# pcb_telemetria.net
KiCad netlist of a schematic drawn in EAGLE
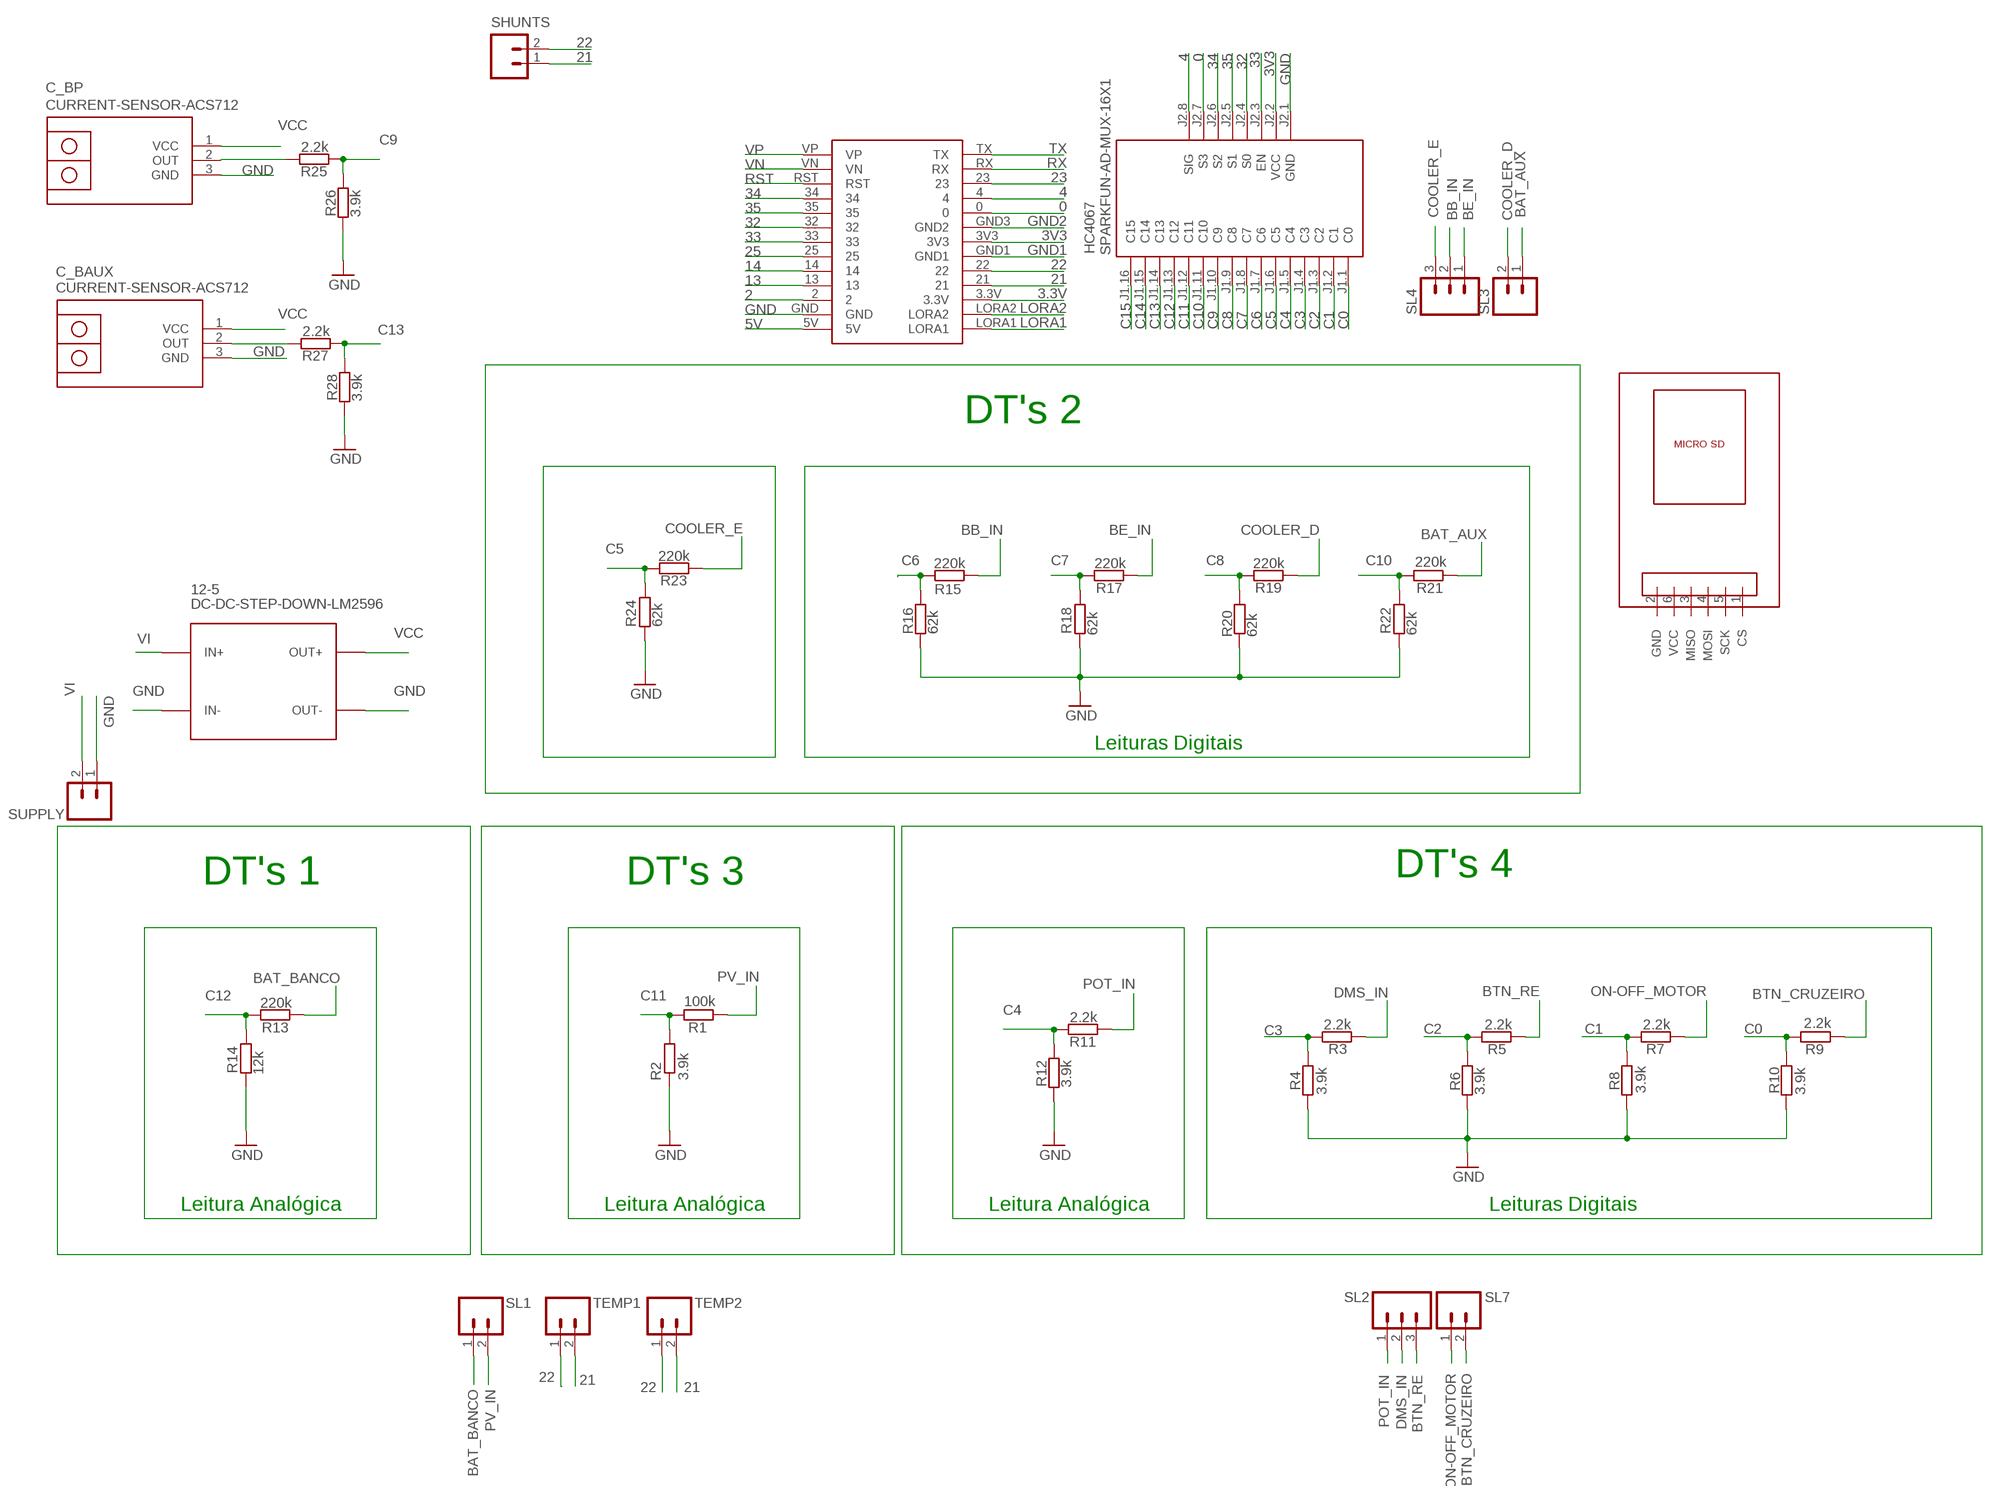
[diagram p0: schematic, sheet 1]

(export (version "E")
  (design (tool "Eeschema 10.0.6"))
  (components
    (comp (ref "12-5")
      (value "DC-DC-STEP-DOWN-LM2596")
      (footprint "eagle-import:DC-DC-STEP-DOWN-LM2596")
      (libsource (lib "eagle-import") (part "DC-DC-STEP-DOWN-LM2596"))
    )
    (comp (ref "C_BAUX")
      (value "CURRENT-SENSOR-ACS712")
      (footprint "eagle-import:CURRENT-SENSOR-ACS712")
      (libsource (lib "eagle-import") (part "CURRENT-SENSOR-ACS712"))
    )
    (comp (ref "C_BP")
      (value "CURRENT-SENSOR-ACS712")
      (footprint "eagle-import:CURRENT-SENSOR-ACS712")
      (libsource (lib "eagle-import") (part "CURRENT-SENSOR-ACS712"))
    )
    (comp (ref "HC4067")
      (value "SPARKFUN-AD-MUX-16X1")
      (footprint "eagle-import:SPARKFUN-AD-MUX-16X1")
      (libsource (lib "eagle-import") (part "SPARKFUN-AD-MUX-16X1"))
    )
    (comp (ref "R1")
      (value "100k")
      (footprint "eagle-import:0204_7")
      (libsource (lib "eagle-import") (part "R-EU_0204/7"))
    )
    (comp (ref "R2")
      (value "3.9k")
      (footprint "eagle-import:0204_7")
      (libsource (lib "eagle-import") (part "R-EU_0204/7"))
    )
    (comp (ref "R3")
      (value "2.2k")
      (footprint "eagle-import:0204_7")
      (libsource (lib "eagle-import") (part "R-EU_0204/7"))
    )
    (comp (ref "R4")
      (value "3.9k")
      (footprint "eagle-import:0204_7")
      (libsource (lib "eagle-import") (part "R-EU_0204/7"))
    )
    (comp (ref "R5")
      (value "2.2k")
      (footprint "eagle-import:0204_7")
      (libsource (lib "eagle-import") (part "R-EU_0204/7"))
    )
    (comp (ref "R6")
      (value "3.9k")
      (footprint "eagle-import:0204_7")
      (libsource (lib "eagle-import") (part "R-EU_0204/7"))
    )
    (comp (ref "R7")
      (value "2.2k")
      (footprint "eagle-import:0204_7")
      (libsource (lib "eagle-import") (part "R-EU_0204/7"))
    )
    (comp (ref "R8")
      (value "3.9k")
      (footprint "eagle-import:0204_7")
      (libsource (lib "eagle-import") (part "R-EU_0204/7"))
    )
    (comp (ref "R9")
      (value "2.2k")
      (footprint "eagle-import:0204_7")
      (libsource (lib "eagle-import") (part "R-EU_0204/7"))
    )
    (comp (ref "R10")
      (value "3.9k")
      (footprint "eagle-import:0204_7")
      (libsource (lib "eagle-import") (part "R-EU_0204/7"))
    )
    (comp (ref "R11")
      (value "2.2k")
      (footprint "eagle-import:0204_7")
      (libsource (lib "eagle-import") (part "R-EU_0204/7"))
    )
    (comp (ref "R12")
      (value "3.9k")
      (footprint "eagle-import:0204_7")
      (libsource (lib "eagle-import") (part "R-EU_0204/7"))
    )
    (comp (ref "R13")
      (value "220k")
      (footprint "eagle-import:0204_7")
      (libsource (lib "eagle-import") (part "R-EU_0204/7"))
    )
    (comp (ref "R14")
      (value "12k")
      (footprint "eagle-import:0204_7")
      (libsource (lib "eagle-import") (part "R-EU_0204/7"))
    )
    (comp (ref "R15")
      (value "220k")
      (footprint "eagle-import:0204_7")
      (libsource (lib "eagle-import") (part "R-EU_0204/7"))
    )
    (comp (ref "R16")
      (value "62k")
      (footprint "eagle-import:0204_7")
      (libsource (lib "eagle-import") (part "R-EU_0204/7"))
    )
    (comp (ref "R17")
      (value "220k")
      (footprint "eagle-import:0204_7")
      (libsource (lib "eagle-import") (part "R-EU_0204/7"))
    )
    (comp (ref "R18")
      (value "62k")
      (footprint "eagle-import:0204_7")
      (libsource (lib "eagle-import") (part "R-EU_0204/7"))
    )
    (comp (ref "R19")
      (value "220k")
      (footprint "eagle-import:0204_7")
      (libsource (lib "eagle-import") (part "R-EU_0204/7"))
    )
    (comp (ref "R20")
      (value "62k")
      (footprint "eagle-import:0204_7")
      (libsource (lib "eagle-import") (part "R-EU_0204/7"))
    )
    (comp (ref "R21")
      (value "220k")
      (footprint "eagle-import:0204_7")
      (libsource (lib "eagle-import") (part "R-EU_0204/7"))
    )
    (comp (ref "R22")
      (value "62k")
      (footprint "eagle-import:0204_7")
      (libsource (lib "eagle-import") (part "R-EU_0204/7"))
    )
    (comp (ref "R23")
      (value "220k")
      (footprint "eagle-import:0204_7")
      (libsource (lib "eagle-import") (part "R-EU_0204/7"))
    )
    (comp (ref "R24")
      (value "62k")
      (footprint "eagle-import:0204_7")
      (libsource (lib "eagle-import") (part "R-EU_0204/7"))
    )
    (comp (ref "R25")
      (value "2.2k")
      (footprint "eagle-import:0204_7")
      (libsource (lib "eagle-import") (part "R-EU_0204/7"))
    )
    (comp (ref "R26")
      (value "3.9k")
      (footprint "eagle-import:0204_7")
      (libsource (lib "eagle-import") (part "R-EU_0204/7"))
    )
    (comp (ref "R27")
      (value "2.2k")
      (footprint "eagle-import:0204_7")
      (libsource (lib "eagle-import") (part "R-EU_0204/7"))
    )
    (comp (ref "R28")
      (value "3.9k")
      (footprint "eagle-import:0204_7")
      (libsource (lib "eagle-import") (part "R-EU_0204/7"))
    )
    (comp (ref "SHUNTS")
      (value "M02")
      (footprint "eagle-import:02P")
      (libsource (lib "eagle-import") (part "M02"))
    )
    (comp (ref "SL1")
      (value "M02")
      (footprint "eagle-import:02P")
      (libsource (lib "eagle-import") (part "M02"))
    )
    (comp (ref "SL2")
      (value "M03")
      (footprint "eagle-import:03P")
      (libsource (lib "eagle-import") (part "M03"))
    )
    (comp (ref "SL3")
      (value "M02")
      (footprint "eagle-import:02P")
      (libsource (lib "eagle-import") (part "M02"))
    )
    (comp (ref "SL4")
      (value "M03")
      (footprint "eagle-import:03P")
      (libsource (lib "eagle-import") (part "M03"))
    )
    (comp (ref "SL7")
      (value "M02")
      (footprint "eagle-import:02P")
      (libsource (lib "eagle-import") (part "M02"))
    )
    (comp (ref "SUPPLY")
      (value "M02")
      (footprint "eagle-import:02P")
      (libsource (lib "eagle-import") (part "M02"))
    )
    (comp (ref "TEMP1")
      (value "M02")
      (footprint "eagle-import:02P")
      (libsource (lib "eagle-import") (part "M02"))
    )
    (comp (ref "TEMP2")
      (value "M02")
      (footprint "eagle-import:02P")
      (libsource (lib "eagle-import") (part "M02"))
    )
    (comp (ref "U$1")
      (value "TTGOBEAM")
      (footprint "eagle-import:TTGOBEAM")
      (libsource (lib "eagle-import") (part "TTGOBEAM"))
    )
    (comp (ref "U$2")
      (value "MICRO_SD_MODULE")
      (footprint "eagle-import:MICRO_SD")
      (libsource (lib "eagle-import") (part "MICRO_SD_MODULE"))
    )
  )
  (nets
    (net (code "1") (name "/0") (class "Default")
      (node (ref "HC4067") (pin "J2.7") (pinfunction "S3_J2.7") (pintype "bidirectional"))
      (node (ref "U$1") (pin "0") (pinfunction "0_0") (pintype "bidirectional"))
    )
    (net (code "2") (name "/2") (class "Default")
      (node (ref "U$1") (pin "2") (pinfunction "2_2") (pintype "bidirectional"))
    )
    (net (code "3") (name "/3.3V") (class "Default")
      (node (ref "U$1") (pin "3.3V") (pinfunction "3.3V_3.3V") (pintype "bidirectional"))
    )
    (net (code "4") (name "/3V3") (class "Default")
      (node (ref "HC4067") (pin "J2.2") (pinfunction "VCC_J2.2") (pintype "power_in"))
      (node (ref "U$1") (pin "3V3") (pinfunction "3V3_3V3") (pintype "bidirectional"))
    )
    (net (code "5") (name "/4") (class "Default")
      (node (ref "HC4067") (pin "J2.8") (pinfunction "SIG_J2.8") (pintype "bidirectional"))
      (node (ref "U$1") (pin "4") (pinfunction "4_4") (pintype "bidirectional"))
    )
    (net (code "6") (name "/5V") (class "Default")
      (node (ref "U$1") (pin "5V") (pinfunction "5V_5V") (pintype "bidirectional"))
    )
    (net (code "7") (name "/13") (class "Default")
      (node (ref "U$1") (pin "13") (pinfunction "13_13") (pintype "bidirectional"))
    )
    (net (code "8") (name "/14") (class "Default")
      (node (ref "U$1") (pin "14") (pinfunction "14_14") (pintype "bidirectional"))
    )
    (net (code "9") (name "/21") (class "Default")
      (node (ref "SHUNTS") (pin "1") (pinfunction "1_1") (pintype "passive"))
      (node (ref "TEMP1") (pin "2") (pinfunction "2_2") (pintype "passive"))
      (node (ref "TEMP2") (pin "2") (pinfunction "2_2") (pintype "passive"))
      (node (ref "U$1") (pin "21") (pinfunction "21_21") (pintype "bidirectional"))
    )
    (net (code "10") (name "/22") (class "Default")
      (node (ref "SHUNTS") (pin "2") (pinfunction "2_2") (pintype "passive"))
      (node (ref "TEMP1") (pin "1") (pinfunction "1_1") (pintype "passive"))
      (node (ref "TEMP2") (pin "1") (pinfunction "1_1") (pintype "passive"))
      (node (ref "U$1") (pin "22") (pinfunction "22_22") (pintype "bidirectional"))
    )
    (net (code "11") (name "/23") (class "Default")
      (node (ref "U$1") (pin "23") (pinfunction "23_23") (pintype "bidirectional"))
    )
    (net (code "12") (name "/25") (class "Default")
      (node (ref "U$1") (pin "25") (pinfunction "25_25") (pintype "bidirectional"))
    )
    (net (code "13") (name "/32") (class "Default")
      (node (ref "HC4067") (pin "J2.4") (pinfunction "S0_J2.4") (pintype "bidirectional"))
      (node (ref "U$1") (pin "32") (pinfunction "32_32") (pintype "bidirectional"))
    )
    (net (code "14") (name "/33") (class "Default")
      (node (ref "HC4067") (pin "J2.3") (pinfunction "EN_J2.3") (pintype "input"))
      (node (ref "U$1") (pin "33") (pinfunction "33_33") (pintype "bidirectional"))
    )
    (net (code "15") (name "/34") (class "Default")
      (node (ref "HC4067") (pin "J2.6") (pinfunction "S2_J2.6") (pintype "bidirectional"))
      (node (ref "U$1") (pin "34") (pinfunction "34_34") (pintype "bidirectional"))
    )
    (net (code "16") (name "/35") (class "Default")
      (node (ref "HC4067") (pin "J2.5") (pinfunction "S1_J2.5") (pintype "bidirectional"))
      (node (ref "U$1") (pin "35") (pinfunction "35_35") (pintype "bidirectional"))
    )
    (net (code "17") (name "/BAT_AUX") (class "Default")
      (node (ref "R21") (pin "2") (pinfunction "2_2") (pintype "passive"))
      (node (ref "SL3") (pin "1") (pinfunction "1_1") (pintype "passive"))
    )
    (net (code "18") (name "/BAT_BANCO") (class "Default")
      (node (ref "R13") (pin "2") (pinfunction "2_2") (pintype "passive"))
      (node (ref "SL1") (pin "1") (pinfunction "1_1") (pintype "passive"))
    )
    (net (code "19") (name "/BB_IN") (class "Default")
      (node (ref "R15") (pin "1") (pinfunction "1_1") (pintype "passive"))
      (node (ref "SL4") (pin "2") (pinfunction "2_2") (pintype "passive"))
    )
    (net (code "20") (name "/BE_IN") (class "Default")
      (node (ref "R17") (pin "2") (pinfunction "2_2") (pintype "passive"))
      (node (ref "SL4") (pin "1") (pinfunction "1_1") (pintype "passive"))
    )
    (net (code "21") (name "/BTN_CRUZEIRO") (class "Default")
      (node (ref "R9") (pin "2") (pinfunction "2_2") (pintype "passive"))
      (node (ref "SL7") (pin "2") (pinfunction "2_2") (pintype "passive"))
    )
    (net (code "22") (name "/BTN_RE") (class "Default")
      (node (ref "R5") (pin "2") (pinfunction "2_2") (pintype "passive"))
      (node (ref "SL2") (pin "3") (pinfunction "3_3") (pintype "passive"))
    )
    (net (code "23") (name "/C0") (class "Default")
      (node (ref "HC4067") (pin "J1.1") (pinfunction "C0_J1.1") (pintype "bidirectional"))
      (node (ref "R10") (pin "2") (pinfunction "2_2") (pintype "passive"))
      (node (ref "R9") (pin "1") (pinfunction "1_1") (pintype "passive"))
    )
    (net (code "24") (name "/C1") (class "Default")
      (node (ref "HC4067") (pin "J1.2") (pinfunction "C1_J1.2") (pintype "bidirectional"))
      (node (ref "R7") (pin "2") (pinfunction "2_2") (pintype "passive"))
      (node (ref "R8") (pin "1") (pinfunction "1_1") (pintype "passive"))
    )
    (net (code "25") (name "/C2") (class "Default")
      (node (ref "HC4067") (pin "J1.3") (pinfunction "C2_J1.3") (pintype "bidirectional"))
      (node (ref "R5") (pin "1") (pinfunction "1_1") (pintype "passive"))
      (node (ref "R6") (pin "2") (pinfunction "2_2") (pintype "passive"))
    )
    (net (code "26") (name "/C3") (class "Default")
      (node (ref "HC4067") (pin "J1.4") (pinfunction "C3_J1.4") (pintype "bidirectional"))
      (node (ref "R3") (pin "2") (pinfunction "2_2") (pintype "passive"))
      (node (ref "R4") (pin "1") (pinfunction "1_1") (pintype "passive"))
    )
    (net (code "27") (name "/C4") (class "Default")
      (node (ref "HC4067") (pin "J1.5") (pinfunction "C4_J1.5") (pintype "bidirectional"))
      (node (ref "R11") (pin "2") (pinfunction "2_2") (pintype "passive"))
      (node (ref "R12") (pin "1") (pinfunction "1_1") (pintype "passive"))
    )
    (net (code "28") (name "/C5") (class "Default")
      (node (ref "HC4067") (pin "J1.6") (pinfunction "C5_J1.6") (pintype "bidirectional"))
      (node (ref "R23") (pin "2") (pinfunction "2_2") (pintype "passive"))
      (node (ref "R24") (pin "1") (pinfunction "1_1") (pintype "passive"))
    )
    (net (code "29") (name "/C6") (class "Default")
      (node (ref "HC4067") (pin "J1.7") (pinfunction "C6_J1.7") (pintype "bidirectional"))
      (node (ref "R15") (pin "2") (pinfunction "2_2") (pintype "passive"))
      (node (ref "R16") (pin "1") (pinfunction "1_1") (pintype "passive"))
    )
    (net (code "30") (name "/C7") (class "Default")
      (node (ref "HC4067") (pin "J1.8") (pinfunction "C7_J1.8") (pintype "bidirectional"))
      (node (ref "R17") (pin "1") (pinfunction "1_1") (pintype "passive"))
      (node (ref "R18") (pin "2") (pinfunction "2_2") (pintype "passive"))
    )
    (net (code "31") (name "/C8") (class "Default")
      (node (ref "HC4067") (pin "J1.9") (pinfunction "C8_J1.9") (pintype "bidirectional"))
      (node (ref "R19") (pin "2") (pinfunction "2_2") (pintype "passive"))
      (node (ref "R20") (pin "1") (pinfunction "1_1") (pintype "passive"))
    )
    (net (code "32") (name "/C9") (class "Default")
      (node (ref "HC4067") (pin "J1.10") (pinfunction "C9_J1.10") (pintype "bidirectional"))
      (node (ref "R25") (pin "1") (pinfunction "1_1") (pintype "passive"))
      (node (ref "R26") (pin "1") (pinfunction "1_1") (pintype "passive"))
    )
    (net (code "33") (name "/C10") (class "Default")
      (node (ref "HC4067") (pin "J1.11") (pinfunction "C10_J1.11") (pintype "bidirectional"))
      (node (ref "R21") (pin "1") (pinfunction "1_1") (pintype "passive"))
      (node (ref "R22") (pin "2") (pinfunction "2_2") (pintype "passive"))
    )
    (net (code "34") (name "/C11") (class "Default")
      (node (ref "HC4067") (pin "J1.12") (pinfunction "C11_J1.12") (pintype "bidirectional"))
      (node (ref "R1") (pin "1") (pinfunction "1_1") (pintype "passive"))
      (node (ref "R2") (pin "2") (pinfunction "2_2") (pintype "passive"))
    )
    (net (code "35") (name "/C12") (class "Default")
      (node (ref "HC4067") (pin "J1.13") (pinfunction "C12_J1.13") (pintype "bidirectional"))
      (node (ref "R13") (pin "1") (pinfunction "1_1") (pintype "passive"))
      (node (ref "R14") (pin "2") (pinfunction "2_2") (pintype "passive"))
    )
    (net (code "36") (name "/C13") (class "Default")
      (node (ref "HC4067") (pin "J1.14") (pinfunction "C13_J1.14") (pintype "bidirectional"))
      (node (ref "R27") (pin "1") (pinfunction "1_1") (pintype "passive"))
      (node (ref "R28") (pin "1") (pinfunction "1_1") (pintype "passive"))
    )
    (net (code "37") (name "/C14") (class "Default")
      (node (ref "HC4067") (pin "J1.15") (pinfunction "C14_J1.15") (pintype "bidirectional"))
    )
    (net (code "38") (name "/C15") (class "Default")
      (node (ref "HC4067") (pin "J1.16") (pinfunction "C15_J1.16") (pintype "bidirectional"))
    )
    (net (code "39") (name "/COOLER_D") (class "Default")
      (node (ref "R19") (pin "1") (pinfunction "1_1") (pintype "passive"))
      (node (ref "SL3") (pin "2") (pinfunction "2_2") (pintype "passive"))
    )
    (net (code "40") (name "/COOLER_E") (class "Default")
      (node (ref "R23") (pin "1") (pinfunction "1_1") (pintype "passive"))
      (node (ref "SL4") (pin "3") (pinfunction "3_3") (pintype "passive"))
    )
    (net (code "41") (name "/DMS_IN") (class "Default")
      (node (ref "R3") (pin "1") (pinfunction "1_1") (pintype "passive"))
      (node (ref "SL2") (pin "2") (pinfunction "2_2") (pintype "passive"))
    )
    (net (code "42") (name "/GND1") (class "Default")
      (node (ref "U$1") (pin "GND1") (pinfunction "GND1_GND1") (pintype "bidirectional"))
    )
    (net (code "43") (name "/GND2") (class "Default")
      (node (ref "U$1") (pin "GND3") (pinfunction "GND2_GND3") (pintype "bidirectional"))
    )
    (net (code "44") (name "/LORA1") (class "Default")
      (node (ref "U$1") (pin "LORA1") (pinfunction "LORA1_LORA1") (pintype "bidirectional"))
    )
    (net (code "45") (name "/LORA2") (class "Default")
      (node (ref "U$1") (pin "LORA2") (pinfunction "LORA2_LORA2") (pintype "bidirectional"))
    )
    (net (code "46") (name "/ON-OFF_MOTOR") (class "Default")
      (node (ref "R7") (pin "1") (pinfunction "1_1") (pintype "passive"))
      (node (ref "SL7") (pin "1") (pinfunction "1_1") (pintype "passive"))
    )
    (net (code "47") (name "/POT_IN") (class "Default")
      (node (ref "R11") (pin "1") (pinfunction "1_1") (pintype "passive"))
      (node (ref "SL2") (pin "1") (pinfunction "1_1") (pintype "passive"))
    )
    (net (code "48") (name "/PV_IN") (class "Default")
      (node (ref "R1") (pin "2") (pinfunction "2_2") (pintype "passive"))
      (node (ref "SL1") (pin "2") (pinfunction "2_2") (pintype "passive"))
    )
    (net (code "49") (name "/RST") (class "Default")
      (node (ref "U$1") (pin "RST") (pinfunction "RST_RST") (pintype "bidirectional"))
    )
    (net (code "50") (name "/RX") (class "Default")
      (node (ref "U$1") (pin "RX") (pinfunction "RX_RX") (pintype "bidirectional"))
    )
    (net (code "51") (name "/TX") (class "Default")
      (node (ref "U$1") (pin "TX") (pinfunction "TX_TX") (pintype "bidirectional"))
    )
    (net (code "52") (name "/VCC") (class "Default")
      (node (ref "12-5") (pin "OUT+") (pinfunction "OUT+_OUT+") (pintype "bidirectional"))
      (node (ref "C_BAUX") (pin "1") (pinfunction "VCC_1") (pintype "power_in"))
      (node (ref "C_BP") (pin "1") (pinfunction "VCC_1") (pintype "power_in"))
    )
    (net (code "53") (name "/VI") (class "Default")
      (node (ref "12-5") (pin "IN+") (pinfunction "IN+_IN+") (pintype "bidirectional"))
      (node (ref "SUPPLY") (pin "2") (pinfunction "2_2") (pintype "passive"))
    )
    (net (code "54") (name "/VN") (class "Default")
      (node (ref "U$1") (pin "VN") (pinfunction "VN_VN") (pintype "bidirectional"))
    )
    (net (code "55") (name "/VP") (class "Default")
      (node (ref "U$1") (pin "VP") (pinfunction "VP_VP") (pintype "bidirectional"))
    )
    (net (code "56") (name "GND") (class "Default")
      (node (ref "12-5") (pin "IN-") (pinfunction "IN-_IN-") (pintype "bidirectional"))
      (node (ref "12-5") (pin "OUT-") (pinfunction "OUT-_OUT-") (pintype "bidirectional"))
      (node (ref "C_BAUX") (pin "3") (pinfunction "GND_3") (pintype "power_in"))
      (node (ref "C_BP") (pin "3") (pinfunction "GND_3") (pintype "power_in"))
      (node (ref "HC4067") (pin "J2.1") (pinfunction "GND_J2.1") (pintype "power_in"))
      (node (ref "R10") (pin "1") (pinfunction "1_1") (pintype "passive"))
      (node (ref "R12") (pin "2") (pinfunction "2_2") (pintype "passive"))
      (node (ref "R14") (pin "1") (pinfunction "1_1") (pintype "passive"))
      (node (ref "R16") (pin "2") (pinfunction "2_2") (pintype "passive"))
      (node (ref "R18") (pin "1") (pinfunction "1_1") (pintype "passive"))
      (node (ref "R2") (pin "1") (pinfunction "1_1") (pintype "passive"))
      (node (ref "R20") (pin "2") (pinfunction "2_2") (pintype "passive"))
      (node (ref "R22") (pin "1") (pinfunction "1_1") (pintype "passive"))
      (node (ref "R24") (pin "2") (pinfunction "2_2") (pintype "passive"))
      (node (ref "R26") (pin "2") (pinfunction "2_2") (pintype "passive"))
      (node (ref "R28") (pin "2") (pinfunction "2_2") (pintype "passive"))
      (node (ref "R4") (pin "2") (pinfunction "2_2") (pintype "passive"))
      (node (ref "R6") (pin "1") (pinfunction "1_1") (pintype "passive"))
      (node (ref "R8") (pin "2") (pinfunction "2_2") (pintype "passive"))
      (node (ref "SUPPLY") (pin "1") (pinfunction "1_1") (pintype "passive"))
      (node (ref "U$1") (pin "GND") (pinfunction "GND_GND") (pintype "bidirectional"))
    )
    (net (code "57") (name "Net-(C_BAUX-OUT)") (class "Default")
      (node (ref "C_BAUX") (pin "2") (pinfunction "OUT_2") (pintype "output"))
      (node (ref "R27") (pin "2") (pinfunction "2_2") (pintype "passive"))
    )
    (net (code "58") (name "Net-(C_BP-OUT)") (class "Default")
      (node (ref "C_BP") (pin "2") (pinfunction "OUT_2") (pintype "output"))
      (node (ref "R25") (pin "2") (pinfunction "2_2") (pintype "passive"))
    )
    (net (code "59") (name "unconnected-(U$2-CS-Pad1)") (class "Default")
      (node (ref "U$2") (pin "1") (pinfunction "CS_1") (pintype "bidirectional"))
    )
    (net (code "60") (name "unconnected-(U$2-GND-Pad2)") (class "Default")
      (node (ref "U$2") (pin "2") (pinfunction "GND_2") (pintype "input"))
    )
    (net (code "61") (name "unconnected-(U$2-MISO-Pad3)") (class "Default")
      (node (ref "U$2") (pin "3") (pinfunction "MISO_3") (pintype "bidirectional"))
    )
    (net (code "62") (name "unconnected-(U$2-MOSI-Pad4)") (class "Default")
      (node (ref "U$2") (pin "4") (pinfunction "MOSI_4") (pintype "bidirectional"))
    )
    (net (code "63") (name "unconnected-(U$2-SCK-Pad5)") (class "Default")
      (node (ref "U$2") (pin "5") (pinfunction "SCK_5") (pintype "bidirectional"))
    )
    (net (code "64") (name "unconnected-(U$2-VCC-Pad6)") (class "Default")
      (node (ref "U$2") (pin "6") (pinfunction "VCC_6") (pintype "input"))
    )
  )
)
